# S02.net
KiCad netlist of a schematic drawn in Altium Designer
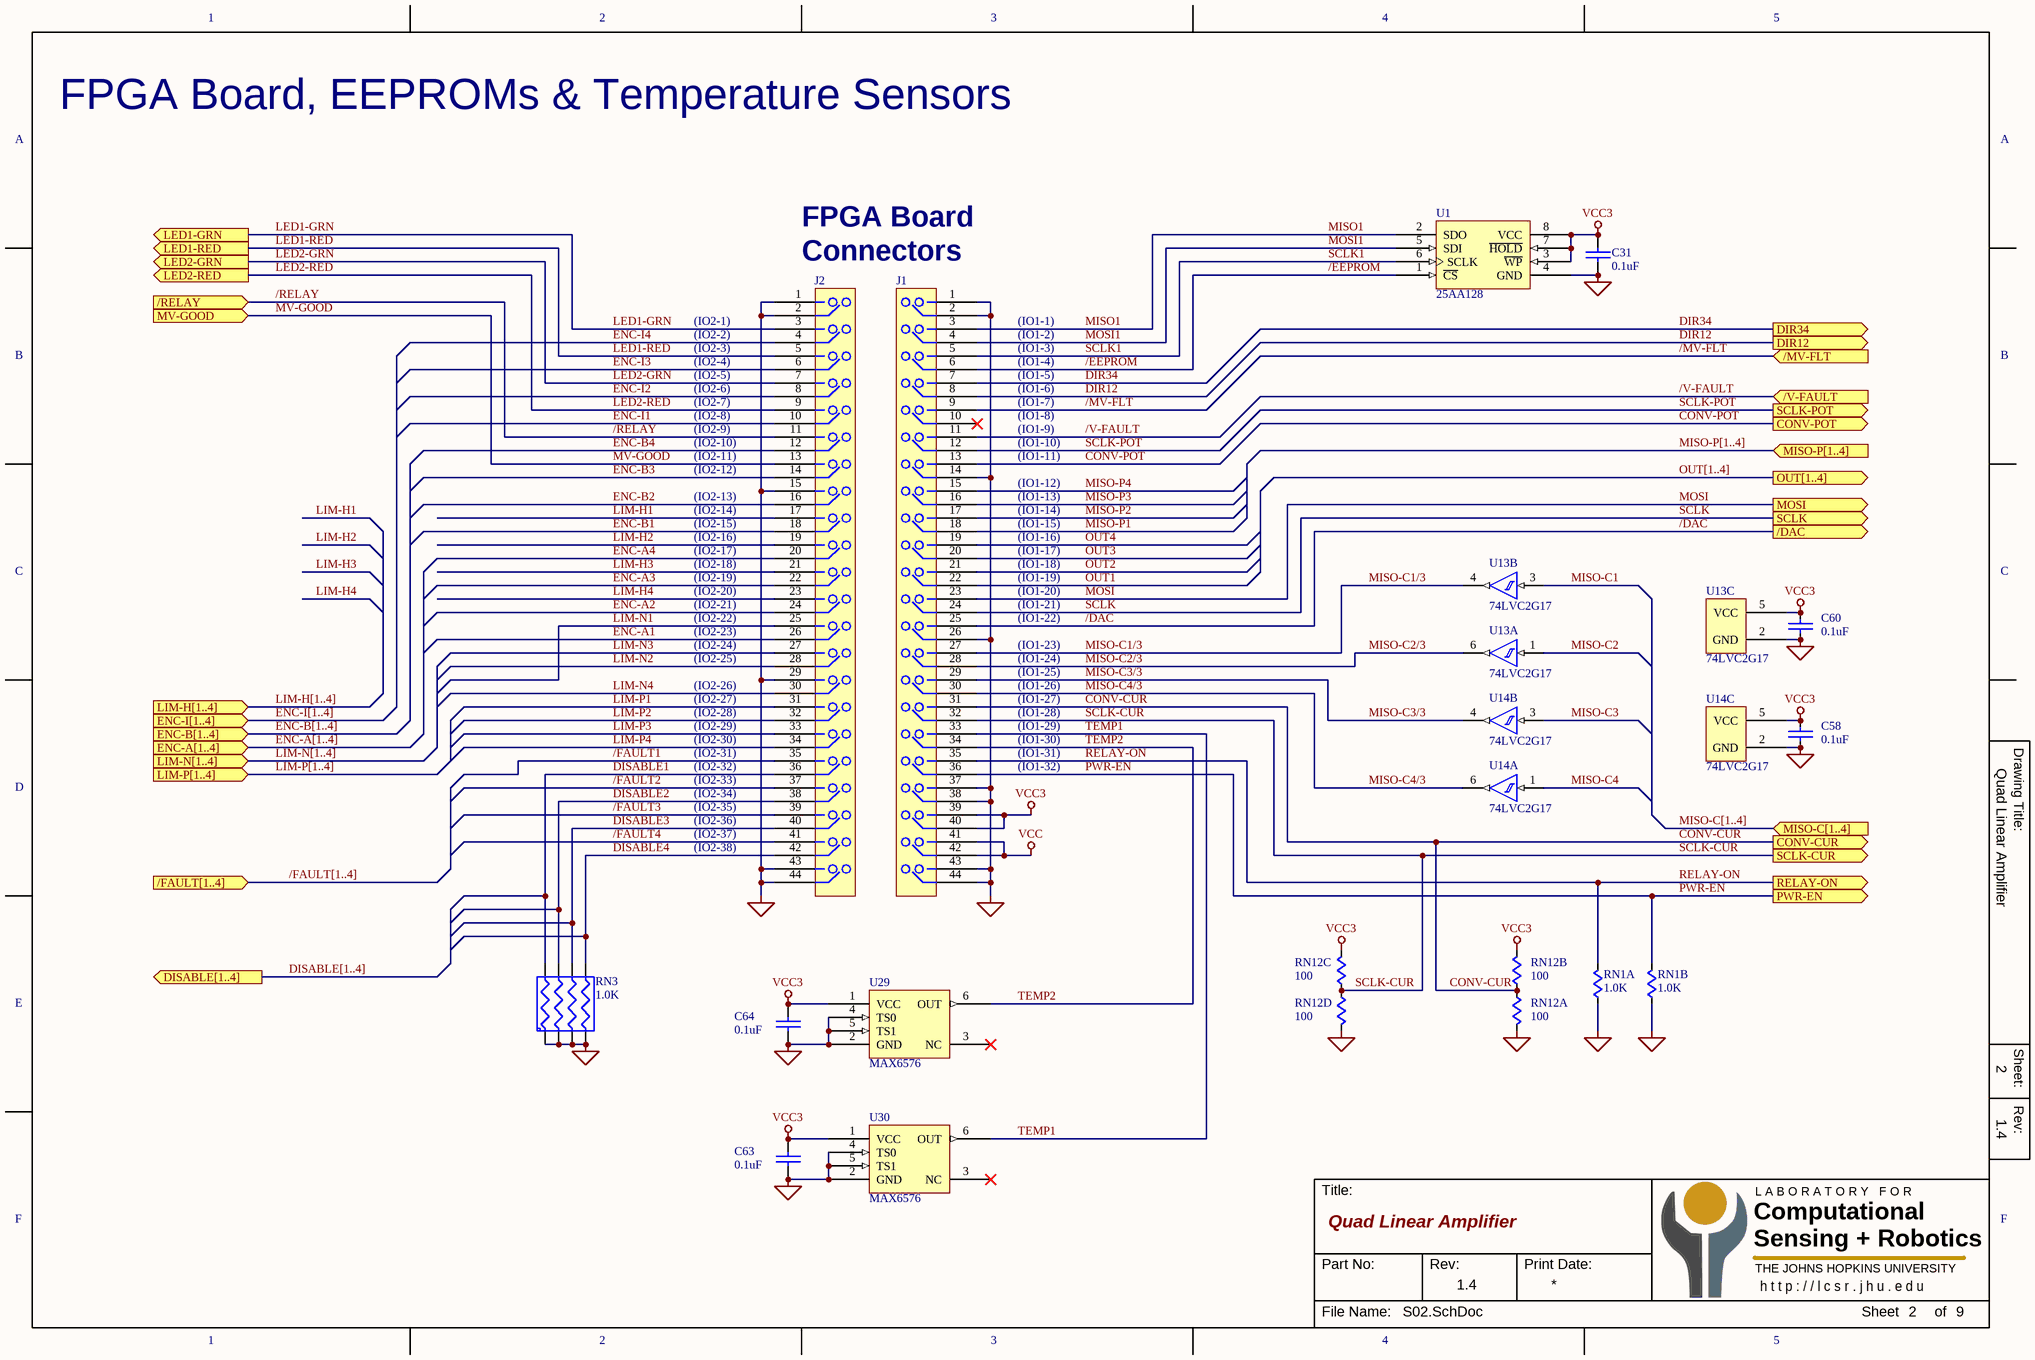
[diagram p0: S02.SchDoc]

(export (version "E")
  (design (tool "Eeschema 10.0.6"))
  (components
    (comp (ref "C31") (value "0.1uF") (footprint "C0603") (libsource (lib "LibJHU") (part "CAP")))
    (comp (ref "C58") (value "0.1uF") (footprint "C0603") (libsource (lib "LibJHU") (part "CAP-MINI")))
    (comp (ref "C60") (value "0.1uF") (footprint "C0603") (libsource (lib "LibJHU") (part "CAP-MINI")))
    (comp (ref "C63") (value "0.1uF") (footprint "C0603") (libsource (lib "LibJHU") (part "CAP")))
    (comp (ref "C64") (value "0.1uF") (footprint "C0603") (libsource (lib "LibJHU") (part "CAP")))
    (comp (ref "J1")
      (value "HEADER 22x2-1")
      (footprint "HDR-22x2-2MM")
      (libsource (lib "LibJHU") (part "HEADER 22x2-1"))
    )
    (comp (ref "J2")
      (value "HEADER 22x2-1")
      (footprint "HDR-22x2-2MM")
      (libsource (lib "LibJHU") (part "HEADER 22x2-1"))
    )
    (comp (ref "RN1")
      (value "1.0K")
      (footprint "RN-742C083")
      (libsource (lib "LibJHU") (part "RN-DISC-SM-4X"))
    )
    (comp (ref "RN3")
      (value "1.0K")
      (footprint "RN-742C083")
      (libsource (lib "LibJHU") (part "RN-DISC-SM-4"))
    )
    (comp (ref "RN12")
      (value "100")
      (footprint "RN-742C083")
      (libsource (lib "LibJHU") (part "RN-DISC-SM-4X"))
    )
    (comp (ref "U1") (value "25AA128") (footprint "TSSOP-8") (libsource (lib "LibJHU") (part "25AA128")))
    (comp (ref "U13")
      (value "74LVC2G17")
      (footprint "SOT-23-6")
      (description "NC7WZ17")
      (libsource (lib "LibJHU") (part "2G17"))
    )
    (comp (ref "U14")
      (value "74LVC2G17")
      (footprint "SOT-23-6")
      (description "NC7WZ17")
      (libsource (lib "LibJHU") (part "2G17"))
    )
    (comp (ref "U29") (value "MAX6576") (footprint "SOT-23-6") (libsource (lib "LibJHU") (part "MAX6576")))
    (comp (ref "U30") (value "MAX6576") (footprint "SOT-23-6") (libsource (lib "LibJHU") (part "MAX6576")))
  )
  (nets
    (net (code "5") (name "/CONV-CUR") (class "Default")
      (node (ref "J1") (pin "31") (pinfunction "31_31") (pintype "passive"))
      (node (ref "RN12") (pin "1") (pinfunction "1_1") (pintype "passive"))
      (node (ref "RN12") (pin "2") (pinfunction "2_2") (pintype "passive"))
    )
    (net (code "6") (name "/CONV-POT") (class "Default")
      (node (ref "J1") (pin "13") (pinfunction "13_13") (pintype "passive"))
    )
    (net (code "7") (name "/DIR12") (class "Default")
      (node (ref "J1") (pin "8") (pinfunction "8_8") (pintype "passive"))
    )
    (net (code "8") (name "/DIR34") (class "Default")
      (node (ref "J1") (pin "7") (pinfunction "7_7") (pintype "passive"))
    )
    (net (code "9") (name "/DISABLE1") (class "Default")
      (node (ref "J2") (pin "36") (pinfunction "36_36") (pintype "passive"))
      (node (ref "RN3") (pin "8") (pinfunction "R1.2_8") (pintype "passive"))
    )
    (net (code "10") (name "/DISABLE2") (class "Default")
      (node (ref "J2") (pin "38") (pinfunction "38_38") (pintype "passive"))
      (node (ref "RN3") (pin "7") (pinfunction "R2.2_7") (pintype "passive"))
    )
    (net (code "11") (name "/DISABLE3") (class "Default")
      (node (ref "J2") (pin "40") (pinfunction "40_40") (pintype "passive"))
      (node (ref "RN3") (pin "6") (pinfunction "R3.2_6") (pintype "passive"))
    )
    (net (code "12") (name "/DISABLE4") (class "Default")
      (node (ref "J2") (pin "42") (pinfunction "42_42") (pintype "passive"))
      (node (ref "RN3") (pin "5") (pinfunction "R4.2_5") (pintype "passive"))
    )
    (net (code "14") (name "/ENC-A1") (class "Default")
      (node (ref "J2") (pin "26") (pinfunction "26_26") (pintype "passive"))
    )
    (net (code "15") (name "/ENC-A2") (class "Default")
      (node (ref "J2") (pin "24") (pinfunction "24_24") (pintype "passive"))
    )
    (net (code "16") (name "/ENC-A3") (class "Default")
      (node (ref "J2") (pin "22") (pinfunction "22_22") (pintype "passive"))
    )
    (net (code "17") (name "/ENC-A4") (class "Default")
      (node (ref "J2") (pin "20") (pinfunction "20_20") (pintype "passive"))
    )
    (net (code "19") (name "/ENC-B1") (class "Default")
      (node (ref "J2") (pin "18") (pinfunction "18_18") (pintype "passive"))
    )
    (net (code "20") (name "/ENC-B2") (class "Default")
      (node (ref "J2") (pin "16") (pinfunction "16_16") (pintype "passive"))
    )
    (net (code "21") (name "/ENC-B3") (class "Default")
      (node (ref "J2") (pin "14") (pinfunction "14_14") (pintype "passive"))
    )
    (net (code "22") (name "/ENC-B4") (class "Default")
      (node (ref "J2") (pin "12") (pinfunction "12_12") (pintype "passive"))
    )
    (net (code "24") (name "/ENC-I1") (class "Default")
      (node (ref "J2") (pin "10") (pinfunction "10_10") (pintype "passive"))
    )
    (net (code "25") (name "/ENC-I2") (class "Default")
      (node (ref "J2") (pin "8") (pinfunction "8_8") (pintype "passive"))
    )
    (net (code "26") (name "/ENC-I3") (class "Default")
      (node (ref "J2") (pin "6") (pinfunction "6_6") (pintype "passive"))
    )
    (net (code "27") (name "/ENC-I4") (class "Default")
      (node (ref "J2") (pin "4") (pinfunction "4_4") (pintype "passive"))
    )
    (net (code "29") (name "/LED1-GRN") (class "Default")
      (node (ref "J2") (pin "3") (pinfunction "3_3") (pintype "passive"))
    )
    (net (code "30") (name "/LED1-RED") (class "Default")
      (node (ref "J2") (pin "5") (pinfunction "5_5") (pintype "passive"))
    )
    (net (code "31") (name "/LED2-GRN") (class "Default")
      (node (ref "J2") (pin "7") (pinfunction "7_7") (pintype "passive"))
    )
    (net (code "32") (name "/LED2-RED") (class "Default")
      (node (ref "J2") (pin "9") (pinfunction "9_9") (pintype "passive"))
    )
    (net (code "33") (name "/LIM-H1") (class "Default")
      (node (ref "J2") (pin "17") (pinfunction "17_17") (pintype "passive"))
    )
    (net (code "34") (name "/LIM-H2") (class "Default")
      (node (ref "J2") (pin "19") (pinfunction "19_19") (pintype "passive"))
    )
    (net (code "35") (name "/LIM-H3") (class "Default")
      (node (ref "J2") (pin "21") (pinfunction "21_21") (pintype "passive"))
    )
    (net (code "36") (name "/LIM-H4") (class "Default")
      (node (ref "J2") (pin "23") (pinfunction "23_23") (pintype "passive"))
    )
    (net (code "38") (name "/LIM-N1") (class "Default")
      (node (ref "J2") (pin "25") (pinfunction "25_25") (pintype "passive"))
    )
    (net (code "39") (name "/LIM-N2") (class "Default")
      (node (ref "J2") (pin "28") (pinfunction "28_28") (pintype "passive"))
    )
    (net (code "40") (name "/LIM-N3") (class "Default")
      (node (ref "J2") (pin "27") (pinfunction "27_27") (pintype "passive"))
    )
    (net (code "41") (name "/LIM-N4") (class "Default")
      (node (ref "J2") (pin "30") (pinfunction "30_30") (pintype "passive"))
    )
    (net (code "43") (name "/LIM-P1") (class "Default")
      (node (ref "J2") (pin "31") (pinfunction "31_31") (pintype "passive"))
    )
    (net (code "44") (name "/LIM-P2") (class "Default")
      (node (ref "J2") (pin "32") (pinfunction "32_32") (pintype "passive"))
    )
    (net (code "45") (name "/LIM-P3") (class "Default")
      (node (ref "J2") (pin "33") (pinfunction "33_33") (pintype "passive"))
    )
    (net (code "46") (name "/LIM-P4") (class "Default")
      (node (ref "J2") (pin "34") (pinfunction "34_34") (pintype "passive"))
    )
    (net (code "48") (name "/MISO-C1") (class "Default") (node (ref "U13") (pin "3") (pintype "input")))
    (net (code "49") (name "/MISO-C1{slash}3") (class "Default")
      (node (ref "J1") (pin "27") (pinfunction "27_27") (pintype "passive"))
      (node (ref "U13") (pin "4") (pintype "output"))
    )
    (net (code "50") (name "/MISO-C2") (class "Default") (node (ref "U13") (pin "1") (pintype "input")))
    (net (code "51") (name "/MISO-C2{slash}3") (class "Default")
      (node (ref "J1") (pin "28") (pinfunction "28_28") (pintype "passive"))
      (node (ref "U13") (pin "6") (pintype "output"))
    )
    (net (code "52") (name "/MISO-C3") (class "Default") (node (ref "U14") (pin "3") (pintype "input")))
    (net (code "53") (name "/MISO-C3{slash}3") (class "Default")
      (node (ref "J1") (pin "29") (pinfunction "29_29") (pintype "passive"))
      (node (ref "U14") (pin "4") (pintype "output"))
    )
    (net (code "54") (name "/MISO-C4") (class "Default") (node (ref "U14") (pin "1") (pintype "input")))
    (net (code "55") (name "/MISO-C4{slash}3") (class "Default")
      (node (ref "J1") (pin "30") (pinfunction "30_30") (pintype "passive"))
      (node (ref "U14") (pin "6") (pintype "output"))
    )
    (net (code "57") (name "/MISO-P1") (class "Default")
      (node (ref "J1") (pin "18") (pinfunction "18_18") (pintype "passive"))
    )
    (net (code "58") (name "/MISO-P2") (class "Default")
      (node (ref "J1") (pin "17") (pinfunction "17_17") (pintype "passive"))
    )
    (net (code "59") (name "/MISO-P3") (class "Default")
      (node (ref "J1") (pin "16") (pinfunction "16_16") (pintype "passive"))
    )
    (net (code "60") (name "/MISO-P4") (class "Default")
      (node (ref "J1") (pin "15") (pinfunction "15_15") (pintype "passive"))
    )
    (net (code "62") (name "/MISO1") (class "Default")
      (node (ref "J1") (pin "3") (pinfunction "3_3") (pintype "passive"))
      (node (ref "U1") (pin "2") (pinfunction "SDO_2") (pintype "tri_state"))
    )
    (net (code "63") (name "/MOSI") (class "Default")
      (node (ref "J1") (pin "23") (pinfunction "23_23") (pintype "passive"))
    )
    (net (code "64") (name "/MOSI1") (class "Default")
      (node (ref "J1") (pin "4") (pinfunction "4_4") (pintype "passive"))
      (node (ref "U1") (pin "5") (pinfunction "SDI_5") (pintype "input"))
    )
    (net (code "65") (name "/MV-GOOD") (class "Default")
      (node (ref "J2") (pin "13") (pinfunction "13_13") (pintype "passive"))
    )
    (net (code "66") (name "/OUT1") (class "Default")
      (node (ref "J1") (pin "22") (pinfunction "22_22") (pintype "passive"))
    )
    (net (code "67") (name "/OUT2") (class "Default")
      (node (ref "J1") (pin "21") (pinfunction "21_21") (pintype "passive"))
    )
    (net (code "68") (name "/OUT3") (class "Default")
      (node (ref "J1") (pin "20") (pinfunction "20_20") (pintype "passive"))
    )
    (net (code "69") (name "/OUT4") (class "Default")
      (node (ref "J1") (pin "19") (pinfunction "19_19") (pintype "passive"))
    )
    (net (code "71") (name "/PWR-EN") (class "Default")
      (node (ref "J1") (pin "36") (pinfunction "36_36") (pintype "passive"))
      (node (ref "RN1") (pin "7") (pinfunction "7_7") (pintype "passive"))
    )
    (net (code "72") (name "/RELAY-ON") (class "Default")
      (node (ref "J1") (pin "35") (pinfunction "35_35") (pintype "passive"))
      (node (ref "RN1") (pin "8") (pinfunction "8_8") (pintype "passive"))
    )
    (net (code "73") (name "/SCLK") (class "Default")
      (node (ref "J1") (pin "24") (pinfunction "24_24") (pintype "passive"))
    )
    (net (code "74") (name "/SCLK-CUR") (class "Default")
      (node (ref "J1") (pin "32") (pinfunction "32_32") (pintype "passive"))
      (node (ref "RN12") (pin "3") (pinfunction "3_3") (pintype "passive"))
      (node (ref "RN12") (pin "4") (pinfunction "4_4") (pintype "passive"))
    )
    (net (code "75") (name "/SCLK-POT") (class "Default")
      (node (ref "J1") (pin "12") (pinfunction "12_12") (pintype "passive"))
    )
    (net (code "76") (name "/SCLK1") (class "Default")
      (node (ref "J1") (pin "5") (pinfunction "5_5") (pintype "passive"))
      (node (ref "U1") (pin "6") (pinfunction "SCLK_6") (pintype "input"))
    )
    (net (code "77") (name "/TEMP1") (class "Default")
      (node (ref "J1") (pin "33") (pinfunction "33_33") (pintype "passive"))
      (node (ref "U30") (pin "6") (pinfunction "OUT_6") (pintype "output"))
    )
    (net (code "78") (name "/TEMP2") (class "Default")
      (node (ref "J1") (pin "34") (pinfunction "34_34") (pintype "passive"))
      (node (ref "U29") (pin "6") (pinfunction "OUT_6") (pintype "output"))
    )
    (net (code "79") (name "/{slash}DAC") (class "Default")
      (node (ref "J1") (pin "25") (pinfunction "25_25") (pintype "passive"))
    )
    (net (code "80") (name "/{slash}EEPROM") (class "Default")
      (node (ref "J1") (pin "6") (pinfunction "6_6") (pintype "passive"))
      (node (ref "U1") (pin "1") (pinfunction "CS_1") (pintype "input"))
    )
    (net (code "81") (name "/{slash}FAULT1") (class "Default")
      (node (ref "J2") (pin "35") (pinfunction "35_35") (pintype "passive"))
    )
    (net (code "82") (name "/{slash}FAULT2") (class "Default")
      (node (ref "J2") (pin "37") (pinfunction "37_37") (pintype "passive"))
    )
    (net (code "83") (name "/{slash}FAULT3") (class "Default")
      (node (ref "J2") (pin "39") (pinfunction "39_39") (pintype "passive"))
    )
    (net (code "84") (name "/{slash}FAULT4") (class "Default")
      (node (ref "J2") (pin "41") (pinfunction "41_41") (pintype "passive"))
    )
    (net (code "86") (name "/{slash}MV-FLT") (class "Default")
      (node (ref "J1") (pin "9") (pinfunction "9_9") (pintype "passive"))
    )
    (net (code "87") (name "/{slash}RELAY") (class "Default")
      (node (ref "J2") (pin "11") (pinfunction "11_11") (pintype "passive"))
    )
    (net (code "88") (name "/{slash}V-FAULT") (class "Default")
      (node (ref "J1") (pin "11") (pinfunction "11_11") (pintype "passive"))
    )
    (net (code "89") (name "GND") (class "Default")
      (node (ref "C31") (pin "2") (pintype "passive"))
      (node (ref "C58") (pin "2") (pintype "passive"))
      (node (ref "C60") (pin "2") (pintype "passive"))
      (node (ref "C63") (pin "2") (pintype "passive"))
      (node (ref "C64") (pin "2") (pintype "passive"))
      (node (ref "J1") (pin "1") (pinfunction "1_1") (pintype "passive"))
      (node (ref "J1") (pin "14") (pinfunction "14_14") (pintype "passive"))
      (node (ref "J1") (pin "2") (pinfunction "2_2") (pintype "passive"))
      (node (ref "J1") (pin "26") (pinfunction "26_26") (pintype "passive"))
      (node (ref "J1") (pin "37") (pinfunction "37_37") (pintype "passive"))
      (node (ref "J1") (pin "38") (pinfunction "38_38") (pintype "passive"))
      (node (ref "J1") (pin "43") (pinfunction "43_43") (pintype "passive"))
      (node (ref "J1") (pin "44") (pinfunction "44_44") (pintype "passive"))
      (node (ref "J2") (pin "1") (pinfunction "1_1") (pintype "passive"))
      (node (ref "J2") (pin "15") (pinfunction "15_15") (pintype "passive"))
      (node (ref "J2") (pin "2") (pinfunction "2_2") (pintype "passive"))
      (node (ref "J2") (pin "29") (pinfunction "29_29") (pintype "passive"))
      (node (ref "J2") (pin "43") (pinfunction "43_43") (pintype "passive"))
      (node (ref "J2") (pin "44") (pinfunction "44_44") (pintype "passive"))
      (node (ref "RN1") (pin "1") (pinfunction "1_1") (pintype "passive"))
      (node (ref "RN1") (pin "2") (pinfunction "2_2") (pintype "passive"))
      (node (ref "RN12") (pin "5") (pinfunction "5_5") (pintype "passive"))
      (node (ref "RN12") (pin "8") (pinfunction "8_8") (pintype "passive"))
      (node (ref "RN3") (pin "1") (pinfunction "R1_1") (pintype "passive"))
      (node (ref "RN3") (pin "2") (pinfunction "R2.1_2") (pintype "passive"))
      (node (ref "RN3") (pin "3") (pinfunction "R3.1_3") (pintype "passive"))
      (node (ref "RN3") (pin "4") (pinfunction "R4.1_4") (pintype "passive"))
      (node (ref "U1") (pin "4") (pinfunction "GND_4") (pintype "power_in"))
      (node (ref "U13") (pin "2") (pinfunction "GND_2") (pintype "power_in"))
      (node (ref "U14") (pin "2") (pinfunction "GND_2") (pintype "power_in"))
      (node (ref "U29") (pin "2") (pinfunction "GND_2") (pintype "power_in"))
      (node (ref "U29") (pin "4") (pinfunction "TS0_4") (pintype "input"))
      (node (ref "U29") (pin "5") (pinfunction "TS1_5") (pintype "input"))
      (node (ref "U30") (pin "2") (pinfunction "GND_2") (pintype "power_in"))
      (node (ref "U30") (pin "4") (pinfunction "TS0_4") (pintype "input"))
      (node (ref "U30") (pin "5") (pinfunction "TS1_5") (pintype "input"))
    )
    (net (code "90") (name "VCC") (class "Default")
      (node (ref "J1") (pin "41") (pinfunction "41_41") (pintype "passive"))
      (node (ref "J1") (pin "42") (pinfunction "42_42") (pintype "passive"))
    )
    (net (code "91") (name "VCC3") (class "Default")
      (node (ref "C31") (pin "1") (pintype "passive"))
      (node (ref "C58") (pin "1") (pintype "passive"))
      (node (ref "C60") (pin "1") (pintype "passive"))
      (node (ref "C63") (pin "1") (pintype "passive"))
      (node (ref "C64") (pin "1") (pintype "passive"))
      (node (ref "J1") (pin "39") (pinfunction "39_39") (pintype "passive"))
      (node (ref "J1") (pin "40") (pinfunction "40_40") (pintype "passive"))
      (node (ref "RN12") (pin "6") (pinfunction "6_6") (pintype "passive"))
      (node (ref "RN12") (pin "7") (pinfunction "7_7") (pintype "passive"))
      (node (ref "U1") (pin "3") (pinfunction "WP_3") (pintype "input"))
      (node (ref "U1") (pin "7") (pinfunction "HOLD_7") (pintype "input"))
      (node (ref "U1") (pin "8") (pinfunction "VCC_8") (pintype "power_in"))
      (node (ref "U13") (pin "5") (pinfunction "VCC_5") (pintype "power_in"))
      (node (ref "U14") (pin "5") (pinfunction "VCC_5") (pintype "power_in"))
      (node (ref "U29") (pin "1") (pinfunction "VCC_1") (pintype "power_in"))
      (node (ref "U30") (pin "1") (pinfunction "VCC_1") (pintype "power_in"))
    )
    (net (code "92") (name "unconnected-(J1-Pad10)") (class "Default")
      (node (ref "J1") (pin "10") (pinfunction "10_10") (pintype "passive+no_connect"))
    )
    (net (code "93") (name "unconnected-(U29-NC-Pad3)") (class "Default")
      (node (ref "U29") (pin "3") (pinfunction "NC_3") (pintype "passive+no_connect"))
    )
    (net (code "94") (name "unconnected-(U30-NC-Pad3)") (class "Default")
      (node (ref "U30") (pin "3") (pinfunction "NC_3") (pintype "passive+no_connect"))
    )
  )
)
